# MDBT42Q.net
KiCad netlist of a schematic drawn in EAGLE
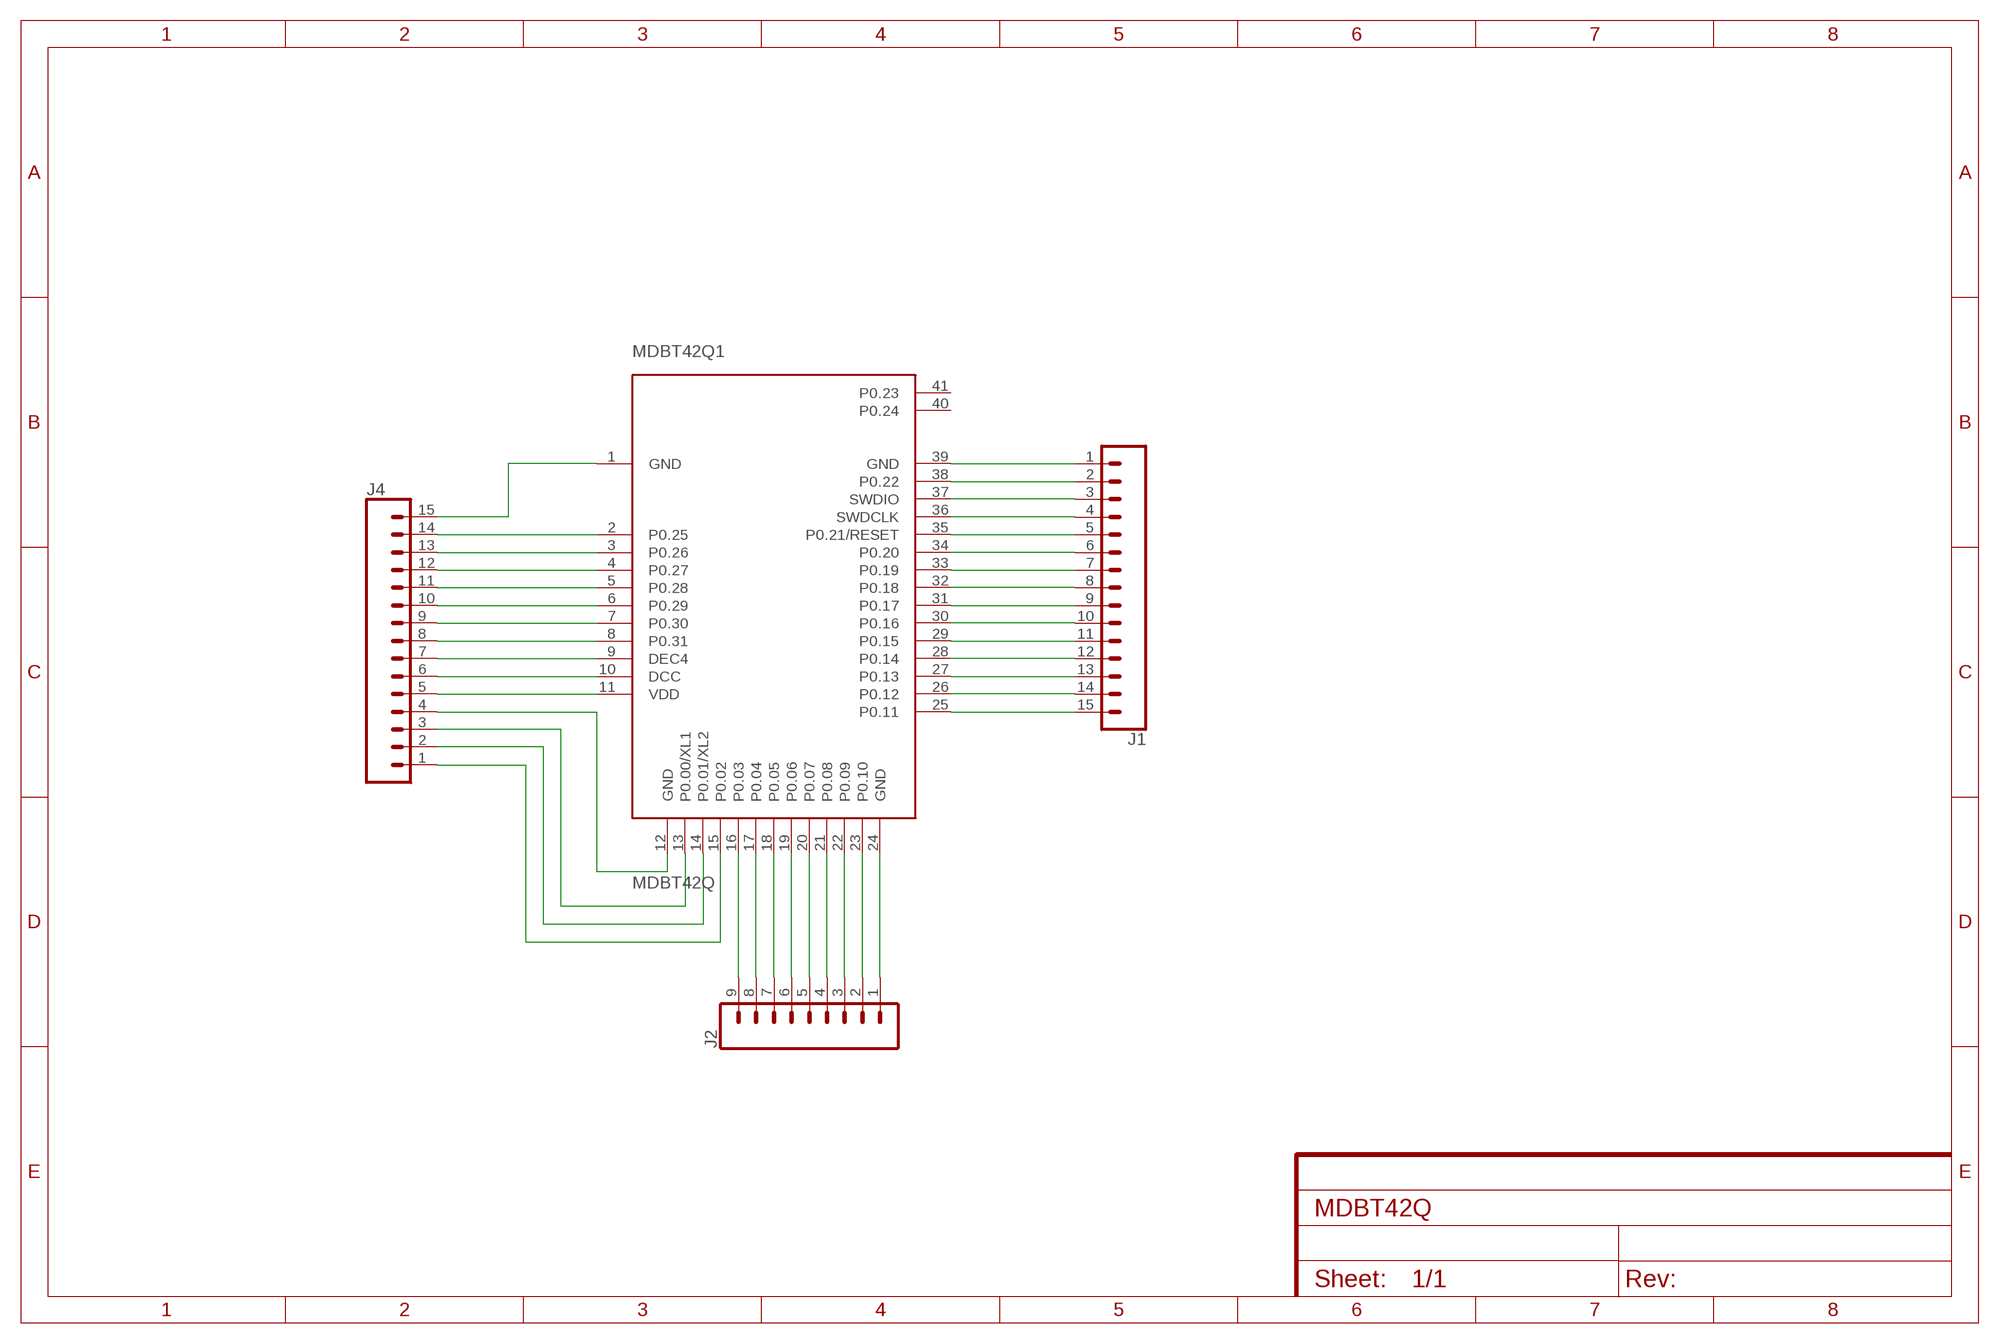
[diagram p0: schematic, sheet 1]

(export (version "E")
  (design (tool "Eeschema 10.0.6"))
  (components
    (comp (ref "J1")
      (value "CONN_15")
      (footprint "eagle-import:1X15")
      (libsource (lib "eagle-import") (part "CONN_15"))
    )
    (comp (ref "J2")
      (value "CONN_09")
      (footprint "eagle-import:1X09")
      (libsource (lib "eagle-import") (part "CONN_09"))
    )
    (comp (ref "J4")
      (value "CONN_15")
      (footprint "eagle-import:1X15")
      (libsource (lib "eagle-import") (part "CONN_15"))
    )
    (comp (ref "MDBT42Q1")
      (value "MDBT42Q")
      (footprint "eagle-import:MDBT42Q")
      (libsource (lib "eagle-import") (part "MDBT42Q"))
    )
  )
  (nets
    (net (code "1") (name "Net-(J1-Pad1)") (class "Default")
      (node (ref "J1") (pin "1") (pinfunction "1_1") (pintype "passive"))
      (node (ref "MDBT42Q1") (pin "39") (pinfunction "GND_39") (pintype "bidirectional"))
    )
    (net (code "2") (name "Net-(J2-Pad1)") (class "Default")
      (node (ref "J2") (pin "1") (pinfunction "1_1") (pintype "passive"))
      (node (ref "MDBT42Q1") (pin "24") (pinfunction "GND_24") (pintype "bidirectional"))
    )
    (net (code "3") (name "Net-(J4-Pad4)") (class "Default")
      (node (ref "J4") (pin "4") (pinfunction "4_4") (pintype "passive"))
      (node (ref "MDBT42Q1") (pin "12") (pinfunction "GND_12") (pintype "bidirectional"))
    )
    (net (code "4") (name "Net-(J4-Pad15)") (class "Default")
      (node (ref "J4") (pin "15") (pinfunction "15_15") (pintype "passive"))
      (node (ref "MDBT42Q1") (pin "1") (pinfunction "GND_1") (pintype "bidirectional"))
    )
    (net (code "5") (name "Net-(MDBT42Q1-DCC)") (class "Default")
      (node (ref "J4") (pin "6") (pinfunction "6_6") (pintype "passive"))
      (node (ref "MDBT42Q1") (pin "10") (pinfunction "DCC_10") (pintype "bidirectional"))
    )
    (net (code "6") (name "Net-(MDBT42Q1-DEC4)") (class "Default")
      (node (ref "J4") (pin "7") (pinfunction "7_7") (pintype "passive"))
      (node (ref "MDBT42Q1") (pin "9") (pinfunction "DEC4_9") (pintype "bidirectional"))
    )
    (net (code "7") (name "Net-(MDBT42Q1-P0.00{slash}XL1)") (class "Default")
      (node (ref "J4") (pin "3") (pinfunction "3_3") (pintype "passive"))
      (node (ref "MDBT42Q1") (pin "13") (pinfunction "P0.00/XL1_13") (pintype "bidirectional"))
    )
    (net (code "8") (name "Net-(MDBT42Q1-P0.01{slash}XL2)") (class "Default")
      (node (ref "J4") (pin "2") (pinfunction "2_2") (pintype "passive"))
      (node (ref "MDBT42Q1") (pin "14") (pinfunction "P0.01/XL2_14") (pintype "bidirectional"))
    )
    (net (code "9") (name "Net-(MDBT42Q1-P0.02)") (class "Default")
      (node (ref "J4") (pin "1") (pinfunction "1_1") (pintype "passive"))
      (node (ref "MDBT42Q1") (pin "15") (pinfunction "P0.02_15") (pintype "bidirectional"))
    )
    (net (code "10") (name "Net-(MDBT42Q1-P0.03)") (class "Default")
      (node (ref "J2") (pin "9") (pinfunction "9_9") (pintype "passive"))
      (node (ref "MDBT42Q1") (pin "16") (pinfunction "P0.03_16") (pintype "bidirectional"))
    )
    (net (code "11") (name "Net-(MDBT42Q1-P0.04)") (class "Default")
      (node (ref "J2") (pin "8") (pinfunction "8_8") (pintype "passive"))
      (node (ref "MDBT42Q1") (pin "17") (pinfunction "P0.04_17") (pintype "bidirectional"))
    )
    (net (code "12") (name "Net-(MDBT42Q1-P0.05)") (class "Default")
      (node (ref "J2") (pin "7") (pinfunction "7_7") (pintype "passive"))
      (node (ref "MDBT42Q1") (pin "18") (pinfunction "P0.05_18") (pintype "bidirectional"))
    )
    (net (code "13") (name "Net-(MDBT42Q1-P0.06)") (class "Default")
      (node (ref "J2") (pin "6") (pinfunction "6_6") (pintype "passive"))
      (node (ref "MDBT42Q1") (pin "19") (pinfunction "P0.06_19") (pintype "bidirectional"))
    )
    (net (code "14") (name "Net-(MDBT42Q1-P0.07)") (class "Default")
      (node (ref "J2") (pin "5") (pinfunction "5_5") (pintype "passive"))
      (node (ref "MDBT42Q1") (pin "20") (pinfunction "P0.07_20") (pintype "bidirectional"))
    )
    (net (code "15") (name "Net-(MDBT42Q1-P0.08)") (class "Default")
      (node (ref "J2") (pin "4") (pinfunction "4_4") (pintype "passive"))
      (node (ref "MDBT42Q1") (pin "21") (pinfunction "P0.08_21") (pintype "bidirectional"))
    )
    (net (code "16") (name "Net-(MDBT42Q1-P0.09)") (class "Default")
      (node (ref "J2") (pin "3") (pinfunction "3_3") (pintype "passive"))
      (node (ref "MDBT42Q1") (pin "22") (pinfunction "P0.09_22") (pintype "bidirectional"))
    )
    (net (code "17") (name "Net-(MDBT42Q1-P0.10)") (class "Default")
      (node (ref "J2") (pin "2") (pinfunction "2_2") (pintype "passive"))
      (node (ref "MDBT42Q1") (pin "23") (pinfunction "P0.10_23") (pintype "bidirectional"))
    )
    (net (code "18") (name "Net-(MDBT42Q1-P0.11)") (class "Default")
      (node (ref "J1") (pin "15") (pinfunction "15_15") (pintype "passive"))
      (node (ref "MDBT42Q1") (pin "25") (pinfunction "P0.11_25") (pintype "bidirectional"))
    )
    (net (code "19") (name "Net-(MDBT42Q1-P0.12)") (class "Default")
      (node (ref "J1") (pin "14") (pinfunction "14_14") (pintype "passive"))
      (node (ref "MDBT42Q1") (pin "26") (pinfunction "P0.12_26") (pintype "bidirectional"))
    )
    (net (code "20") (name "Net-(MDBT42Q1-P0.13)") (class "Default")
      (node (ref "J1") (pin "13") (pinfunction "13_13") (pintype "passive"))
      (node (ref "MDBT42Q1") (pin "27") (pinfunction "P0.13_27") (pintype "bidirectional"))
    )
    (net (code "21") (name "Net-(MDBT42Q1-P0.14)") (class "Default")
      (node (ref "J1") (pin "12") (pinfunction "12_12") (pintype "passive"))
      (node (ref "MDBT42Q1") (pin "28") (pinfunction "P0.14_28") (pintype "bidirectional"))
    )
    (net (code "22") (name "Net-(MDBT42Q1-P0.15)") (class "Default")
      (node (ref "J1") (pin "11") (pinfunction "11_11") (pintype "passive"))
      (node (ref "MDBT42Q1") (pin "29") (pinfunction "P0.15_29") (pintype "bidirectional"))
    )
    (net (code "23") (name "Net-(MDBT42Q1-P0.16)") (class "Default")
      (node (ref "J1") (pin "10") (pinfunction "10_10") (pintype "passive"))
      (node (ref "MDBT42Q1") (pin "30") (pinfunction "P0.16_30") (pintype "bidirectional"))
    )
    (net (code "24") (name "Net-(MDBT42Q1-P0.17)") (class "Default")
      (node (ref "J1") (pin "9") (pinfunction "9_9") (pintype "passive"))
      (node (ref "MDBT42Q1") (pin "31") (pinfunction "P0.17_31") (pintype "bidirectional"))
    )
    (net (code "25") (name "Net-(MDBT42Q1-P0.18)") (class "Default")
      (node (ref "J1") (pin "8") (pinfunction "8_8") (pintype "passive"))
      (node (ref "MDBT42Q1") (pin "32") (pinfunction "P0.18_32") (pintype "bidirectional"))
    )
    (net (code "26") (name "Net-(MDBT42Q1-P0.19)") (class "Default")
      (node (ref "J1") (pin "7") (pinfunction "7_7") (pintype "passive"))
      (node (ref "MDBT42Q1") (pin "33") (pinfunction "P0.19_33") (pintype "bidirectional"))
    )
    (net (code "27") (name "Net-(MDBT42Q1-P0.20)") (class "Default")
      (node (ref "J1") (pin "6") (pinfunction "6_6") (pintype "passive"))
      (node (ref "MDBT42Q1") (pin "34") (pinfunction "P0.20_34") (pintype "bidirectional"))
    )
    (net (code "28") (name "Net-(MDBT42Q1-P0.21{slash}RESET)") (class "Default")
      (node (ref "J1") (pin "5") (pinfunction "5_5") (pintype "passive"))
      (node (ref "MDBT42Q1") (pin "35") (pinfunction "P0.21/RESET_35") (pintype "bidirectional"))
    )
    (net (code "29") (name "Net-(MDBT42Q1-P0.22)") (class "Default")
      (node (ref "J1") (pin "2") (pinfunction "2_2") (pintype "passive"))
      (node (ref "MDBT42Q1") (pin "38") (pinfunction "P0.22_38") (pintype "bidirectional"))
    )
    (net (code "30") (name "Net-(MDBT42Q1-P0.25)") (class "Default")
      (node (ref "J4") (pin "14") (pinfunction "14_14") (pintype "passive"))
      (node (ref "MDBT42Q1") (pin "2") (pinfunction "P0.25_2") (pintype "bidirectional"))
    )
    (net (code "31") (name "Net-(MDBT42Q1-P0.26)") (class "Default")
      (node (ref "J4") (pin "13") (pinfunction "13_13") (pintype "passive"))
      (node (ref "MDBT42Q1") (pin "3") (pinfunction "P0.26_3") (pintype "bidirectional"))
    )
    (net (code "32") (name "Net-(MDBT42Q1-P0.27)") (class "Default")
      (node (ref "J4") (pin "12") (pinfunction "12_12") (pintype "passive"))
      (node (ref "MDBT42Q1") (pin "4") (pinfunction "P0.27_4") (pintype "bidirectional"))
    )
    (net (code "33") (name "Net-(MDBT42Q1-P0.28)") (class "Default")
      (node (ref "J4") (pin "11") (pinfunction "11_11") (pintype "passive"))
      (node (ref "MDBT42Q1") (pin "5") (pinfunction "P0.28_5") (pintype "bidirectional"))
    )
    (net (code "34") (name "Net-(MDBT42Q1-P0.29)") (class "Default")
      (node (ref "J4") (pin "10") (pinfunction "10_10") (pintype "passive"))
      (node (ref "MDBT42Q1") (pin "6") (pinfunction "P0.29_6") (pintype "bidirectional"))
    )
    (net (code "35") (name "Net-(MDBT42Q1-P0.30)") (class "Default")
      (node (ref "J4") (pin "9") (pinfunction "9_9") (pintype "passive"))
      (node (ref "MDBT42Q1") (pin "7") (pinfunction "P0.30_7") (pintype "bidirectional"))
    )
    (net (code "36") (name "Net-(MDBT42Q1-P0.31)") (class "Default")
      (node (ref "J4") (pin "8") (pinfunction "8_8") (pintype "passive"))
      (node (ref "MDBT42Q1") (pin "8") (pinfunction "P0.31_8") (pintype "bidirectional"))
    )
    (net (code "37") (name "Net-(MDBT42Q1-SWDCLK)") (class "Default")
      (node (ref "J1") (pin "4") (pinfunction "4_4") (pintype "passive"))
      (node (ref "MDBT42Q1") (pin "36") (pinfunction "SWDCLK_36") (pintype "bidirectional"))
    )
    (net (code "38") (name "Net-(MDBT42Q1-SWDIO)") (class "Default")
      (node (ref "J1") (pin "3") (pinfunction "3_3") (pintype "passive"))
      (node (ref "MDBT42Q1") (pin "37") (pinfunction "SWDIO_37") (pintype "bidirectional"))
    )
    (net (code "39") (name "Net-(MDBT42Q1-VDD)") (class "Default")
      (node (ref "J4") (pin "5") (pinfunction "5_5") (pintype "passive"))
      (node (ref "MDBT42Q1") (pin "11") (pinfunction "VDD_11") (pintype "bidirectional"))
    )
    (net (code "40") (name "unconnected-(MDBT42Q1-P0.23-Pad41)") (class "Default")
      (node (ref "MDBT42Q1") (pin "41") (pinfunction "P0.23_41") (pintype "bidirectional"))
    )
    (net (code "41") (name "unconnected-(MDBT42Q1-P0.24-Pad40)") (class "Default")
      (node (ref "MDBT42Q1") (pin "40") (pinfunction "P0.24_40") (pintype "bidirectional"))
    )
  )
)
